# Diag_586220_Cassette.net
KiCad netlist of a schematic drawn in EAGLE
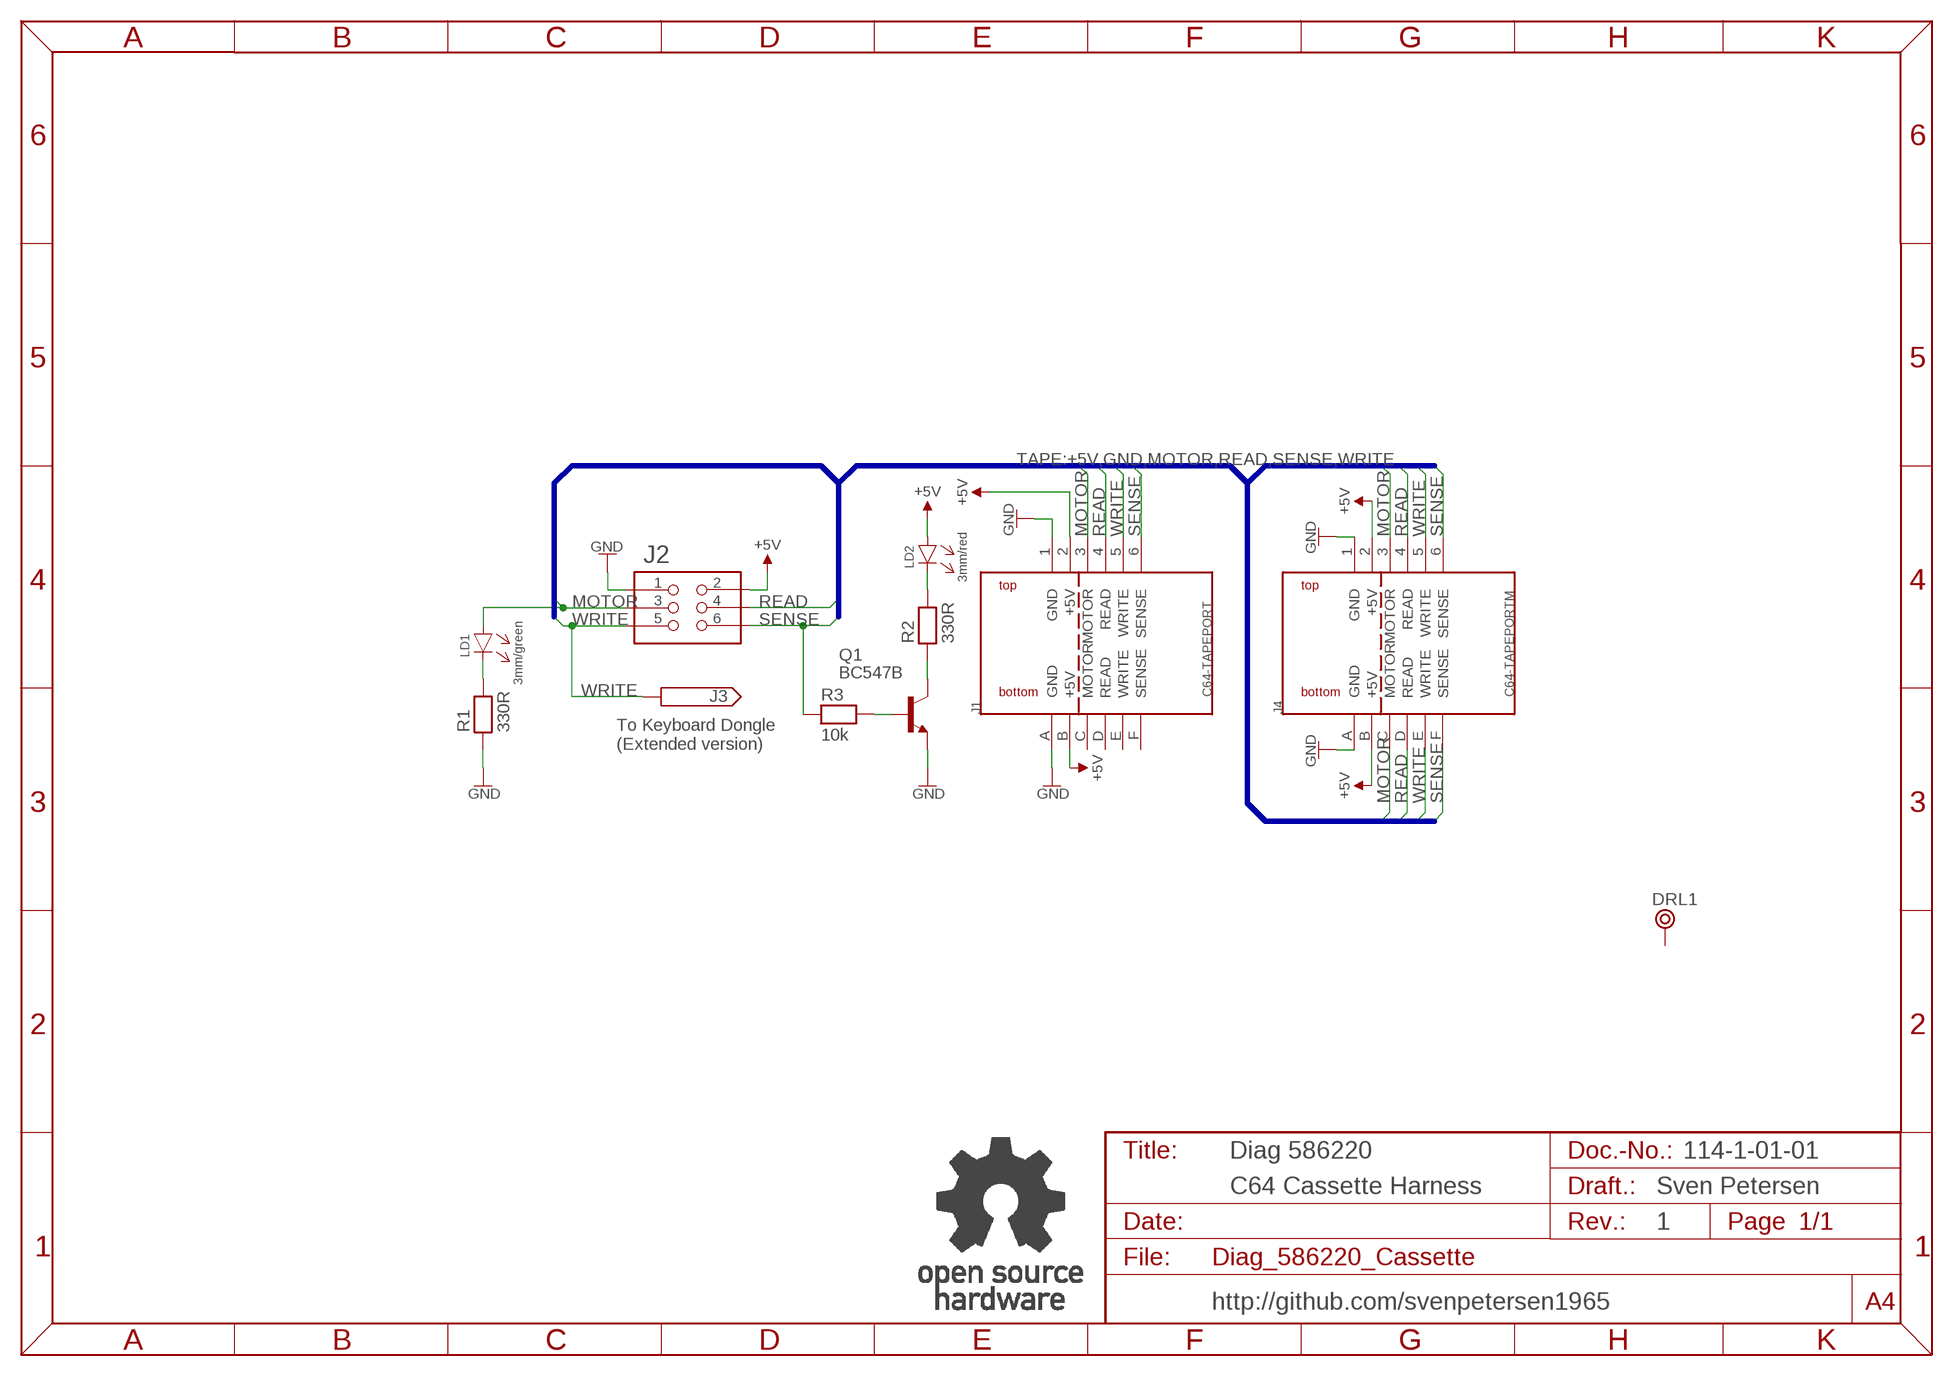
[diagram p0: schematic, sheet 1]

(export (version "E")
  (design (tool "Eeschema 10.0.6"))
  (components
    (comp (ref "DRL1")
      (value "BOHR3,5")
      (footprint "eagle-import:BOHR3,5")
      (libsource (lib "eagle-import") (part "BOHR3,5"))
    )
    (comp (ref "J1")
      (value "C64-TAPEPORT")
      (footprint "eagle-import:TAPEPORT")
      (libsource (lib "eagle-import") (part "C64-TAPEPORT"))
    )
    (comp (ref "J2")
      (value "2X03WV")
      (footprint "eagle-import:2X03WV")
      (libsource (lib "eagle-import") (part "2X03WV"))
    )
    (comp (ref "J3")
      (value "PINHD-1X1")
      (footprint "eagle-import:1X01")
      (libsource (lib "eagle-import") (part "PINHD-1X1"))
    )
    (comp (ref "J4")
      (value "C64-TAPEPORTM")
      (footprint "eagle-import:TAPEPORT_M")
      (libsource (lib "eagle-import") (part "C64-TAPEPORTM"))
    )
    (comp (ref "LD1")
      (value "3mm/green")
      (footprint "eagle-import:3MM")
      (libsource (lib "eagle-import") (part "3MM"))
    )
    (comp (ref "LD2")
      (value "3mm/red")
      (footprint "eagle-import:3MM")
      (libsource (lib "eagle-import") (part "3MM"))
    )
    (comp (ref "Q1")
      (value "BC547B")
      (footprint "eagle-import:TO92")
      (libsource (lib "eagle-import") (part "BC547B"))
    )
    (comp (ref "R1")
      (value "330R")
      (footprint "eagle-import:R-10")
      (libsource (lib "eagle-import") (part "RES04"))
    )
    (comp (ref "R2")
      (value "330R")
      (footprint "eagle-import:R-10")
      (libsource (lib "eagle-import") (part "RES04"))
    )
    (comp (ref "R3")
      (value "10k")
      (footprint "eagle-import:R-10")
      (libsource (lib "eagle-import") (part "RES04"))
    )
    (comp (ref "U$18")
      (value "OPEN_SOURCE_HW")
      (footprint "eagle-import:OPENHW")
      (libsource (lib "eagle-import") (part "OPEN_SOURCE_HW"))
    )
  )
  (nets
    (net (code "2") (name "+5V") (class "Default")
      (node (ref "J1") (pin "2") (pinfunction "+5V_2") (pintype "power_in"))
      (node (ref "J1") (pin "B") (pinfunction "+5V_B") (pintype "power_in"))
      (node (ref "J2") (pin "2") (pinfunction "2_2") (pintype "passive"))
      (node (ref "J4") (pin "2") (pinfunction "+5V_2") (pintype "power_in"))
      (node (ref "J4") (pin "B") (pinfunction "+5V_B") (pintype "power_in"))
      (node (ref "LD2") (pin "A") (pinfunction "A_A") (pintype "bidirectional"))
    )
    (net (code "3") (name "/MOTOR") (class "Default")
      (node (ref "J1") (pin "3") (pinfunction "MOTOR_3") (pintype "output"))
      (node (ref "J2") (pin "3") (pinfunction "3_3") (pintype "passive"))
      (node (ref "J4") (pin "3") (pinfunction "MOTOR_3") (pintype "output"))
      (node (ref "J4") (pin "C") (pinfunction "MOTOR_C") (pintype "output"))
      (node (ref "LD1") (pin "A") (pinfunction "A_A") (pintype "bidirectional"))
    )
    (net (code "4") (name "/READ") (class "Default")
      (node (ref "J1") (pin "4") (pinfunction "READ_4") (pintype "input"))
      (node (ref "J2") (pin "4") (pinfunction "4_4") (pintype "passive"))
      (node (ref "J4") (pin "4") (pinfunction "READ_4") (pintype "input"))
      (node (ref "J4") (pin "D") (pinfunction "READ_D") (pintype "input"))
    )
    (net (code "5") (name "/SENSE") (class "Default")
      (node (ref "J1") (pin "6") (pinfunction "SENSE_6") (pintype "input"))
      (node (ref "J2") (pin "6") (pinfunction "6_6") (pintype "passive"))
      (node (ref "J4") (pin "6") (pinfunction "SENSE_6") (pintype "input"))
      (node (ref "J4") (pin "F") (pinfunction "SENSE_F") (pintype "input"))
      (node (ref "R3") (pin "1") (pinfunction "1_1") (pintype "passive"))
    )
    (net (code "6") (name "/WRITE") (class "Default")
      (node (ref "J1") (pin "5") (pinfunction "WRITE_5") (pintype "output"))
      (node (ref "J2") (pin "5") (pinfunction "5_5") (pintype "passive"))
      (node (ref "J3") (pin "1") (pinfunction "1_1") (pintype "passive"))
      (node (ref "J4") (pin "5") (pinfunction "WRITE_5") (pintype "output"))
      (node (ref "J4") (pin "E") (pinfunction "WRITE_E") (pintype "output"))
    )
    (net (code "8") (name "GND") (class "Default")
      (node (ref "J1") (pin "1") (pinfunction "GND_1") (pintype "power_in"))
      (node (ref "J1") (pin "A") (pinfunction "GND_A") (pintype "power_in"))
      (node (ref "J2") (pin "1") (pinfunction "1_1") (pintype "passive"))
      (node (ref "J4") (pin "1") (pinfunction "GND_1") (pintype "power_in"))
      (node (ref "J4") (pin "A") (pinfunction "GND_A") (pintype "power_in"))
      (node (ref "Q1") (pin "1") (pinfunction "E_1") (pintype "passive"))
      (node (ref "R1") (pin "1") (pinfunction "1_1") (pintype "passive"))
    )
    (net (code "9") (name "Net-(LD1-K)") (class "Default")
      (node (ref "LD1") (pin "C") (pinfunction "K_C") (pintype "bidirectional"))
      (node (ref "R1") (pin "2") (pinfunction "2_2") (pintype "passive"))
    )
    (net (code "10") (name "Net-(LD2-K)") (class "Default")
      (node (ref "LD2") (pin "C") (pinfunction "K_C") (pintype "bidirectional"))
      (node (ref "R2") (pin "2") (pinfunction "2_2") (pintype "passive"))
    )
    (net (code "11") (name "Net-(Q1-B)") (class "Default")
      (node (ref "Q1") (pin "2") (pinfunction "B_2") (pintype "passive"))
      (node (ref "R3") (pin "2") (pinfunction "2_2") (pintype "passive"))
    )
    (net (code "12") (name "Net-(Q1-C)") (class "Default")
      (node (ref "Q1") (pin "3") (pinfunction "C_3") (pintype "passive"))
      (node (ref "R2") (pin "1") (pinfunction "1_1") (pintype "passive"))
    )
    (net (code "13") (name "unconnected-(DRL1-PadP$1)") (class "Default")
      (node (ref "DRL1") (pin "P$1") (pinfunction "P$1_P$1") (pintype "passive"))
    )
    (net (code "14") (name "unconnected-(J1-MOTOR-PadC)") (class "Default")
      (node (ref "J1") (pin "C") (pinfunction "MOTOR_C") (pintype "output"))
    )
    (net (code "15") (name "unconnected-(J1-READ-PadD)") (class "Default")
      (node (ref "J1") (pin "D") (pinfunction "READ_D") (pintype "input"))
    )
    (net (code "16") (name "unconnected-(J1-SENSE-PadF)") (class "Default")
      (node (ref "J1") (pin "F") (pinfunction "SENSE_F") (pintype "input"))
    )
    (net (code "17") (name "unconnected-(J1-WRITE-PadE)") (class "Default")
      (node (ref "J1") (pin "E") (pinfunction "WRITE_E") (pintype "output"))
    )
  )
)
